# GKmini_SMD_final.net
KiCad netlist of a schematic drawn in EAGLE
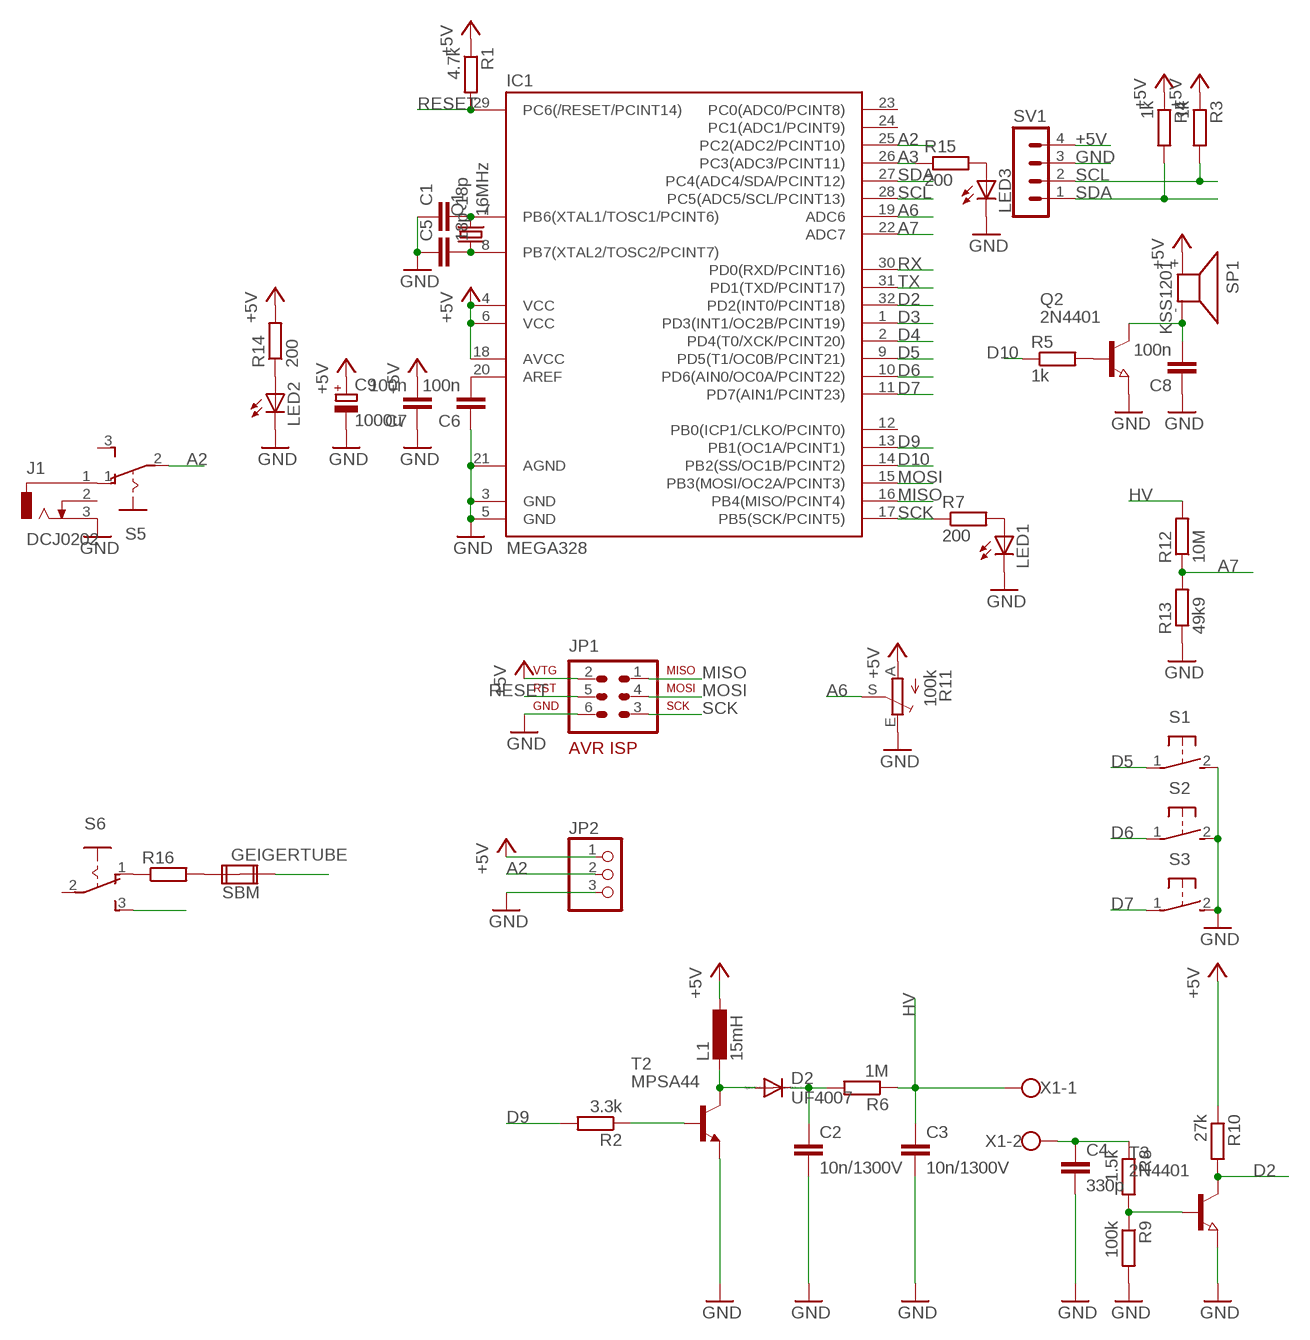
[diagram p0: schematic, sheet 1]

(export (version "E")
  (design (tool "Eeschema 10.0.6"))
  (components
    (comp (ref "C1")
      (value "18p")
      (footprint "eagle-import:C0805")
      (libsource (lib "eagle-import") (part "C-EUC0805"))
    )
    (comp (ref "C2")
      (value "10n/1300V")
      (footprint "eagle-import:C150-054X183")
      (libsource (lib "eagle-import") (part "rcl-igi_C-EU150-054X183"))
    )
    (comp (ref "C3")
      (value "10n/1300V")
      (footprint "eagle-import:C150-054X183")
      (libsource (lib "eagle-import") (part "rcl-igi_C-EU150-054X183"))
    )
    (comp (ref "C4")
      (value "330p")
      (footprint "eagle-import:C0805K")
      (libsource (lib "eagle-import") (part "C-EUC0805K"))
    )
    (comp (ref "C5")
      (value "18p")
      (footprint "eagle-import:C0805")
      (libsource (lib "eagle-import") (part "C-EUC0805"))
    )
    (comp (ref "C6")
      (value "100n")
      (footprint "eagle-import:C0805")
      (libsource (lib "eagle-import") (part "C-EUC0805"))
    )
    (comp (ref "C7")
      (value "100n")
      (footprint "eagle-import:C0805")
      (libsource (lib "eagle-import") (part "C-EUC0805"))
    )
    (comp (ref "C8")
      (value "100n")
      (footprint "eagle-import:C0805")
      (libsource (lib "eagle-import") (part "C-EUC0805"))
    )
    (comp (ref "C9")
      (value "1000u")
      (footprint "eagle-import:153CLV-1012")
      (libsource (lib "eagle-import") (part "CPOL-EU153CLV-1012"))
    )
    (comp (ref "D2")
      (value "UF4007")
      (footprint "eagle-import:C1702-05")
      (libsource (lib "eagle-import") (part "DIODE-C1702-05"))
    )
    (comp (ref "GEIGERTUBE")
      (value "SBM")
      (footprint "eagle-import:SBM")
      (libsource (lib "eagle-import") (part "SBM21"))
    )
    (comp (ref "IC1")
      (value "MEGA328")
      (footprint "eagle-import:TQFP32-08")
      (libsource (lib "eagle-import") (part "MEGA48/88/168-AU"))
    )
    (comp (ref "J1")
      (value "DCJ0202")
      (footprint "eagle-import:DCJ0202")
      (libsource (lib "eagle-import") (part "DCJ0202"))
    )
    (comp (ref "JP1")
      (value "AVR-ISP-6R")
      (footprint "eagle-import:AVR-ISP-6R")
      (libsource (lib "eagle-import") (part "AVR-ISP-6R"))
    )
    (comp (ref "JP2")
      (value "PINHD-1X3")
      (footprint "eagle-import:1X03")
      (libsource (lib "eagle-import") (part "PINHD-1X3"))
    )
    (comp (ref "L1")
      (value "15mH")
      (footprint "eagle-import:6000-XXXX-RC")
      (libsource (lib "eagle-import") (part "L-EU6000-XXX-RC"))
    )
    (comp (ref "LED1")
      (value "LED3MM")
      (footprint "eagle-import:LED3MM")
      (libsource (lib "eagle-import") (part "LED3MM"))
    )
    (comp (ref "LED2")
      (value "LED3MM")
      (footprint "eagle-import:LED3MM")
      (libsource (lib "eagle-import") (part "LED3MM"))
    )
    (comp (ref "LED3")
      (value "LED3MM")
      (footprint "eagle-import:LED3MM")
      (libsource (lib "eagle-import") (part "LED3MM"))
    )
    (comp (ref "Q1")
      (value "16MHz")
      (footprint "eagle-import:HC49UP")
      (libsource (lib "eagle-import") (part "CRYSTALHC49UP"))
    )
    (comp (ref "Q2")
      (value "2N4401")
      (footprint "eagle-import:SOT23W")
      (libsource (lib "eagle-import") (part "NPN-TRANSISTOR_SOT23W"))
    )
    (comp (ref "R1")
      (value "4.7k")
      (footprint "eagle-import:R0805")
      (libsource (lib "eagle-import") (part "R-EU_R0805"))
    )
    (comp (ref "R2")
      (value "3.3k")
      (footprint "eagle-import:R0805")
      (libsource (lib "eagle-import") (part "R-EU_R0805"))
    )
    (comp (ref "R3")
      (value "1k")
      (footprint "eagle-import:R0805")
      (libsource (lib "eagle-import") (part "R-EU_R0805"))
    )
    (comp (ref "R4")
      (value "1k")
      (footprint "eagle-import:R0805")
      (libsource (lib "eagle-import") (part "R-EU_R0805"))
    )
    (comp (ref "R5")
      (value "1k")
      (footprint "eagle-import:R0805")
      (libsource (lib "eagle-import") (part "R-EU_R0805"))
    )
    (comp (ref "R6")
      (value "1M")
      (footprint "eagle-import:0207_5V")
      (libsource (lib "eagle-import") (part "rcl-igi_R-EU_0207/5V"))
    )
    (comp (ref "R7")
      (value "200")
      (footprint "eagle-import:R0805")
      (libsource (lib "eagle-import") (part "R-EU_R0805"))
    )
    (comp (ref "R8")
      (value "1.5k")
      (footprint "eagle-import:R0805W")
      (libsource (lib "eagle-import") (part "R-EU_R0805W"))
    )
    (comp (ref "R9")
      (value "100k")
      (footprint "eagle-import:R0805W")
      (libsource (lib "eagle-import") (part "R-EU_R0805W"))
    )
    (comp (ref "R10")
      (value "27k")
      (footprint "eagle-import:R0805W")
      (libsource (lib "eagle-import") (part "R-EU_R0805W"))
    )
    (comp (ref "R11")
      (value "100k")
      (footprint "eagle-import:S64Y")
      (libsource (lib "eagle-import") (part "TRIM_EU-S64Y"))
    )
    (comp (ref "R12")
      (value "10M")
      (footprint "eagle-import:R0805")
      (libsource (lib "eagle-import") (part "R-EU_R0805"))
    )
    (comp (ref "R13")
      (value "49k9")
      (footprint "eagle-import:R0805")
      (libsource (lib "eagle-import") (part "R-EU_R0805"))
    )
    (comp (ref "R14")
      (value "200")
      (footprint "eagle-import:R0805")
      (libsource (lib "eagle-import") (part "R-EU_R0805"))
    )
    (comp (ref "R15")
      (value "200")
      (footprint "eagle-import:R0805")
      (libsource (lib "eagle-import") (part "R-EU_R0805"))
    )
    (comp (ref "R16")
      (value "R-EU_R1206W")
      (footprint "eagle-import:R1206W")
      (libsource (lib "eagle-import") (part "resistor_R-EU_R1206W"))
    )
    (comp (ref "S1")
      (value "31-XX")
      (footprint "eagle-import:B3F-31XX")
      (fields (field (name "MPN") "B3F-3100"))
      (libsource (lib "eagle-import") (part "31-XX"))
    )
    (comp (ref "S2")
      (value "31-XX")
      (footprint "eagle-import:B3F-31XX")
      (fields (field (name "MPN") "B3F-3100"))
      (libsource (lib "eagle-import") (part "31-XX"))
    )
    (comp (ref "S3")
      (value "31-XX")
      (footprint "eagle-import:B3F-31XX")
      (fields (field (name "MPN") "B3F-3100"))
      (libsource (lib "eagle-import") (part "31-XX"))
    )
    (comp (ref "S5")
      (value "255SB")
      (footprint "eagle-import:255SB")
      (libsource (lib "eagle-import") (part "255SB"))
    )
    (comp (ref "S6")
      (value "255SB")
      (footprint "eagle-import:255SB")
      (libsource (lib "eagle-import") (part "255SB"))
    )
    (comp (ref "SP1")
      (value "KSS1201")
      (footprint "eagle-import:KSS1201")
      (libsource (lib "eagle-import") (part "KSS1201"))
    )
    (comp (ref "SV1")
      (value "MA04-1")
      (footprint "eagle-import:MA04-1")
      (libsource (lib "eagle-import") (part "MA04-1"))
    )
    (comp (ref "T2")
      (value "MPSA44")
      (footprint "eagle-import:TO92-EBC-OVAL")
      (libsource (lib "eagle-import") (part "2N2222"))
    )
    (comp (ref "T3")
      (value "2N4401")
      (footprint "eagle-import:SOT23W")
      (libsource (lib "eagle-import") (part "NPN-TRANSISTOR_SOT23W"))
    )
    (comp (ref "X1")
      (value "W237-102")
      (footprint "eagle-import:W237-102")
      (fields (field (name "MPN") "237-102"))
      (libsource (lib "eagle-import") (part "W237-102"))
    )
  )
  (nets
    (net (code "1") (name "+5V") (class "Default")
      (node (ref "C7") (pin "2") (pinfunction "2_2") (pintype "passive"))
      (node (ref "C9") (pin "+") (pinfunction "+_+") (pintype "passive"))
      (node (ref "IC1") (pin "18") (pinfunction "AVCC_18") (pintype "passive"))
      (node (ref "IC1") (pin "4") (pinfunction "VCC_4") (pintype "power_in"))
      (node (ref "IC1") (pin "6") (pinfunction "VCC_6") (pintype "power_in"))
      (node (ref "JP1") (pin "2") (pinfunction "2_2") (pintype "passive"))
      (node (ref "JP2") (pin "1") (pinfunction "1_1") (pintype "passive"))
      (node (ref "L1") (pin "1") (pinfunction "1_1") (pintype "passive"))
      (node (ref "R1") (pin "1") (pinfunction "1_1") (pintype "passive"))
      (node (ref "R10") (pin "1") (pinfunction "1_1") (pintype "passive"))
      (node (ref "R11") (pin "A") (pinfunction "A_A") (pintype "passive"))
      (node (ref "R14") (pin "2") (pinfunction "2_2") (pintype "passive"))
      (node (ref "R3") (pin "1") (pinfunction "1_1") (pintype "passive"))
      (node (ref "R4") (pin "1") (pinfunction "1_1") (pintype "passive"))
      (node (ref "SP1") (pin "+") (pinfunction "1_+") (pintype "passive"))
      (node (ref "SV1") (pin "4") (pinfunction "4_4") (pintype "passive"))
    )
    (net (code "2") (name "/A2") (class "Default")
      (node (ref "IC1") (pin "25") (pinfunction "PC2(ADC2/PCINT10)_25") (pintype "bidirectional"))
      (node (ref "JP2") (pin "2") (pinfunction "2_2") (pintype "passive"))
      (node (ref "S5") (pin "2") (pinfunction "P_2") (pintype "passive"))
    )
    (net (code "3") (name "/A3") (class "Default")
      (node (ref "IC1") (pin "26") (pinfunction "PC3(ADC3/PCINT11)_26") (pintype "bidirectional"))
      (node (ref "R15") (pin "1") (pinfunction "1_1") (pintype "passive"))
    )
    (net (code "4") (name "/A6") (class "Default")
      (node (ref "IC1") (pin "19") (pinfunction "ADC6_19") (pintype "passive"))
      (node (ref "R11") (pin "S") (pinfunction "S_S") (pintype "passive"))
    )
    (net (code "5") (name "/A7") (class "Default")
      (node (ref "IC1") (pin "22") (pinfunction "ADC7_22") (pintype "passive"))
      (node (ref "R12") (pin "1") (pinfunction "1_1") (pintype "passive"))
      (node (ref "R13") (pin "2") (pinfunction "2_2") (pintype "passive"))
    )
    (net (code "6") (name "/D2") (class "Default")
      (node (ref "IC1") (pin "32") (pinfunction "PD2(INT0/PCINT18)_32") (pintype "bidirectional"))
      (node (ref "R10") (pin "2") (pinfunction "2_2") (pintype "passive"))
      (node (ref "T3") (pin "2") (pinfunction "C_2") (pintype "passive"))
    )
    (net (code "7") (name "/D3") (class "Default")
      (node (ref "IC1") (pin "1") (pinfunction "PD3(INT1/OC2B/PCINT19)_1") (pintype "bidirectional"))
    )
    (net (code "8") (name "/D4") (class "Default")
      (node (ref "IC1") (pin "2") (pinfunction "PD4(T0/XCK/PCINT20)_2") (pintype "bidirectional"))
    )
    (net (code "9") (name "/D5") (class "Default")
      (node (ref "IC1") (pin "9") (pinfunction "PD5(T1/OC0B/PCINT21)_9") (pintype "bidirectional"))
      (node (ref "S1") (pin "1") (pinfunction "P_1") (pintype "passive"))
    )
    (net (code "10") (name "/D6") (class "Default")
      (node (ref "IC1") (pin "10") (pinfunction "PD6(AIN0/OC0A/PCINT22)_10") (pintype "bidirectional"))
      (node (ref "S2") (pin "1") (pinfunction "P_1") (pintype "passive"))
    )
    (net (code "11") (name "/D7") (class "Default")
      (node (ref "IC1") (pin "11") (pinfunction "PD7(AIN1/PCINT23)_11") (pintype "bidirectional"))
      (node (ref "S3") (pin "1") (pinfunction "P_1") (pintype "passive"))
    )
    (net (code "12") (name "/D9") (class "Default")
      (node (ref "IC1") (pin "13") (pinfunction "PB1(OC1A/PCINT1)_13") (pintype "bidirectional"))
      (node (ref "R2") (pin "2") (pinfunction "2_2") (pintype "passive"))
    )
    (net (code "13") (name "/D10") (class "Default")
      (node (ref "IC1") (pin "14") (pinfunction "PB2(SS/OC1B/PCINT2)_14") (pintype "bidirectional"))
      (node (ref "R5") (pin "1") (pinfunction "1_1") (pintype "passive"))
    )
    (net (code "14") (name "/HV") (class "Default")
      (node (ref "C3") (pin "1") (pinfunction "1_1") (pintype "passive"))
      (node (ref "R12") (pin "2") (pinfunction "2_2") (pintype "passive"))
      (node (ref "R6") (pin "1") (pinfunction "1_1") (pintype "passive"))
      (node (ref "X1") (pin "1") (pinfunction "KL_1") (pintype "passive"))
    )
    (net (code "15") (name "/MISO") (class "Default")
      (node (ref "IC1") (pin "16") (pinfunction "PB4(MISO/PCINT4)_16") (pintype "bidirectional"))
      (node (ref "JP1") (pin "1") (pinfunction "1_1") (pintype "passive"))
    )
    (net (code "16") (name "/MOSI") (class "Default")
      (node (ref "IC1") (pin "15") (pinfunction "PB3(MOSI/OC2A/PCINT3)_15") (pintype "bidirectional"))
      (node (ref "JP1") (pin "4") (pinfunction "4_4") (pintype "passive"))
    )
    (net (code "17") (name "/RESET") (class "Default")
      (node (ref "IC1") (pin "29") (pinfunction "PC6(/RESET/PCINT14)_29") (pintype "bidirectional"))
      (node (ref "JP1") (pin "5") (pinfunction "5_5") (pintype "passive"))
      (node (ref "R1") (pin "2") (pinfunction "2_2") (pintype "passive"))
    )
    (net (code "18") (name "/RX") (class "Default")
      (node (ref "IC1") (pin "30") (pinfunction "PD0(RXD/PCINT16)_30") (pintype "bidirectional"))
    )
    (net (code "19") (name "/SCK") (class "Default")
      (node (ref "IC1") (pin "17") (pinfunction "PB5(SCK/PCINT5)_17") (pintype "bidirectional"))
      (node (ref "JP1") (pin "3") (pinfunction "3_3") (pintype "passive"))
      (node (ref "R7") (pin "1") (pinfunction "1_1") (pintype "passive"))
    )
    (net (code "20") (name "/SCL") (class "Default")
      (node (ref "IC1") (pin "28") (pinfunction "PC5(ADC5/SCL/PCINT13)_28") (pintype "bidirectional"))
      (node (ref "R3") (pin "2") (pinfunction "2_2") (pintype "passive"))
      (node (ref "SV1") (pin "2") (pinfunction "2_2") (pintype "passive"))
    )
    (net (code "21") (name "/SDA") (class "Default")
      (node (ref "IC1") (pin "27") (pinfunction "PC4(ADC4/SDA/PCINT12)_27") (pintype "bidirectional"))
      (node (ref "R4") (pin "2") (pinfunction "2_2") (pintype "passive"))
      (node (ref "SV1") (pin "1") (pinfunction "1_1") (pintype "passive"))
    )
    (net (code "22") (name "/TX") (class "Default")
      (node (ref "IC1") (pin "31") (pinfunction "PD1(TXD/PCINT17)_31") (pintype "bidirectional"))
    )
    (net (code "23") (name "GND") (class "Default")
      (node (ref "C1") (pin "1") (pinfunction "1_1") (pintype "passive"))
      (node (ref "C2") (pin "2") (pinfunction "2_2") (pintype "passive"))
      (node (ref "C3") (pin "2") (pinfunction "2_2") (pintype "passive"))
      (node (ref "C4") (pin "2") (pinfunction "2_2") (pintype "passive"))
      (node (ref "C5") (pin "1") (pinfunction "1_1") (pintype "passive"))
      (node (ref "C6") (pin "1") (pinfunction "1_1") (pintype "passive"))
      (node (ref "C7") (pin "1") (pinfunction "1_1") (pintype "passive"))
      (node (ref "C8") (pin "1") (pinfunction "1_1") (pintype "passive"))
      (node (ref "C9") (pin "-") (pinfunction "-_-") (pintype "passive"))
      (node (ref "IC1") (pin "21") (pinfunction "AGND_21") (pintype "power_in"))
      (node (ref "IC1") (pin "3") (pinfunction "GND_3") (pintype "power_in"))
      (node (ref "IC1") (pin "5") (pinfunction "GND_5") (pintype "power_in"))
      (node (ref "J1") (pin "3") (pinfunction "3_3") (pintype "passive"))
      (node (ref "JP1") (pin "6") (pinfunction "6_6") (pintype "passive"))
      (node (ref "JP2") (pin "3") (pinfunction "3_3") (pintype "passive"))
      (node (ref "LED1") (pin "K") (pinfunction "C_K") (pintype "passive"))
      (node (ref "LED2") (pin "K") (pinfunction "C_K") (pintype "passive"))
      (node (ref "LED3") (pin "K") (pinfunction "C_K") (pintype "passive"))
      (node (ref "Q2") (pin "3") (pinfunction "E_3") (pintype "passive"))
      (node (ref "R11") (pin "E") (pinfunction "E_E") (pintype "passive"))
      (node (ref "R13") (pin "1") (pinfunction "1_1") (pintype "passive"))
      (node (ref "R9") (pin "2") (pinfunction "2_2") (pintype "passive"))
      (node (ref "S1") (pin "2") (pinfunction "S_2") (pintype "passive"))
      (node (ref "S2") (pin "2") (pinfunction "S_2") (pintype "passive"))
      (node (ref "S3") (pin "2") (pinfunction "S_2") (pintype "passive"))
      (node (ref "SV1") (pin "3") (pinfunction "3_3") (pintype "passive"))
      (node (ref "T2") (pin "E") (pinfunction "E_E") (pintype "passive"))
      (node (ref "T3") (pin "3") (pinfunction "E_3") (pintype "passive"))
    )
    (net (code "24") (name "Net-(C2-Pad1)") (class "Default")
      (node (ref "C2") (pin "1") (pinfunction "1_1") (pintype "passive"))
      (node (ref "D2") (pin "C") (pinfunction "C_C") (pintype "passive"))
      (node (ref "R6") (pin "2") (pinfunction "2_2") (pintype "passive"))
    )
    (net (code "25") (name "Net-(D2-PadA)") (class "Default")
      (node (ref "D2") (pin "A") (pinfunction "A_A") (pintype "passive"))
      (node (ref "L1") (pin "2") (pinfunction "2_2") (pintype "passive"))
      (node (ref "T2") (pin "C") (pinfunction "C_C") (pintype "passive"))
    )
    (net (code "26") (name "Net-(GEIGERTUBE-Pad1A)") (class "Default")
      (node (ref "GEIGERTUBE") (pin "1A") (pinfunction "1A_1A") (pintype "passive"))
      (node (ref "R16") (pin "2") (pinfunction "2_2") (pintype "passive"))
    )
    (net (code "27") (name "Net-(IC1-AREF)") (class "Default")
      (node (ref "C6") (pin "2") (pinfunction "2_2") (pintype "passive"))
      (node (ref "IC1") (pin "20") (pinfunction "AREF_20") (pintype "passive"))
    )
    (net (code "28") (name "Net-(IC1-PB6(XTAL1{slash}TOSC1{slash}PCINT6))") (class "Default")
      (node (ref "C1") (pin "2") (pinfunction "2_2") (pintype "passive"))
      (node (ref "IC1") (pin "7") (pinfunction "PB6(XTAL1/TOSC1/PCINT6)_7") (pintype "bidirectional"))
      (node (ref "Q1") (pin "2") (pinfunction "2_2") (pintype "passive"))
    )
    (net (code "29") (name "Net-(IC1-PB7(XTAL2{slash}TOSC2{slash}PCINT7))") (class "Default")
      (node (ref "C5") (pin "2") (pinfunction "2_2") (pintype "passive"))
      (node (ref "IC1") (pin "8") (pinfunction "PB7(XTAL2/TOSC2/PCINT7)_8") (pintype "bidirectional"))
      (node (ref "Q1") (pin "1") (pinfunction "1_1") (pintype "passive"))
    )
    (net (code "30") (name "Net-(LED1-PadA)") (class "Default")
      (node (ref "LED1") (pin "A") (pinfunction "A_A") (pintype "passive"))
      (node (ref "R7") (pin "2") (pinfunction "2_2") (pintype "passive"))
    )
    (net (code "31") (name "Net-(LED2-PadA)") (class "Default")
      (node (ref "LED2") (pin "A") (pinfunction "A_A") (pintype "passive"))
      (node (ref "R14") (pin "1") (pinfunction "1_1") (pintype "passive"))
    )
    (net (code "32") (name "Net-(LED3-PadA)") (class "Default")
      (node (ref "LED3") (pin "A") (pinfunction "A_A") (pintype "passive"))
      (node (ref "R15") (pin "2") (pinfunction "2_2") (pintype "passive"))
    )
    (net (code "33") (name "Net-(Q2-B)") (class "Default")
      (node (ref "Q2") (pin "1") (pinfunction "B_1") (pintype "passive"))
      (node (ref "R5") (pin "2") (pinfunction "2_2") (pintype "passive"))
    )
    (net (code "34") (name "Net-(Q2-C)") (class "Default")
      (node (ref "C8") (pin "2") (pinfunction "2_2") (pintype "passive"))
      (node (ref "Q2") (pin "2") (pinfunction "C_2") (pintype "passive"))
      (node (ref "SP1") (pin "-") (pinfunction "2_-") (pintype "passive"))
    )
    (net (code "35") (name "Net-(R2-Pad1)") (class "Default")
      (node (ref "R2") (pin "1") (pinfunction "1_1") (pintype "passive"))
      (node (ref "T2") (pin "B") (pinfunction "B_B") (pintype "passive"))
    )
    (net (code "36") (name "Net-(S5-O)") (class "Default")
      (node (ref "J1") (pin "1") (pinfunction "1_1") (pintype "passive"))
      (node (ref "S5") (pin "1") (pinfunction "O_1") (pintype "passive"))
    )
    (net (code "37") (name "Net-(S6-O)") (class "Default")
      (node (ref "R16") (pin "1") (pinfunction "1_1") (pintype "passive"))
      (node (ref "S6") (pin "1") (pinfunction "O_1") (pintype "passive"))
    )
    (net (code "38") (name "Net-(T3-B)") (class "Default")
      (node (ref "R8") (pin "2") (pinfunction "2_2") (pintype "passive"))
      (node (ref "R9") (pin "1") (pinfunction "1_1") (pintype "passive"))
      (node (ref "T3") (pin "1") (pinfunction "B_1") (pintype "passive"))
    )
    (net (code "39") (name "Net-(X1B-KL)") (class "Default")
      (node (ref "C4") (pin "1") (pinfunction "1_1") (pintype "passive"))
      (node (ref "R8") (pin "1") (pinfunction "1_1") (pintype "passive"))
      (node (ref "X1") (pin "2") (pinfunction "KL_2") (pintype "passive"))
    )
    (net (code "40") (name "unconnected-(GEIGERTUBE-Pad1B)") (class "Default")
      (node (ref "GEIGERTUBE") (pin "1B") (pinfunction "1B_1B") (pintype "passive"))
    )
    (net (code "41") (name "unconnected-(GEIGERTUBE-Pad2A)") (class "Default")
      (node (ref "GEIGERTUBE") (pin "2A") (pinfunction "2A_2A") (pintype "passive"))
    )
    (net (code "42") (name "unconnected-(GEIGERTUBE-Pad2B)") (class "Default")
      (node (ref "GEIGERTUBE") (pin "2B") (pinfunction "2B_2B") (pintype "passive"))
    )
    (net (code "43") (name "unconnected-(IC1-PB0(ICP1{slash}CLKO{slash}PCINT0)-Pad12)") (class "Default")
      (node (ref "IC1") (pin "12") (pinfunction "PB0(ICP1/CLKO/PCINT0)_12") (pintype "bidirectional"))
    )
    (net (code "44") (name "unconnected-(IC1-PC0(ADC0{slash}PCINT8)-Pad23)") (class "Default")
      (node (ref "IC1") (pin "23") (pinfunction "PC0(ADC0/PCINT8)_23") (pintype "bidirectional"))
    )
    (net (code "45") (name "unconnected-(IC1-PC1(ADC1{slash}PCINT9)-Pad24)") (class "Default")
      (node (ref "IC1") (pin "24") (pinfunction "PC1(ADC1/PCINT9)_24") (pintype "bidirectional"))
    )
    (net (code "46") (name "unconnected-(J1-Pad2)") (class "Default")
      (node (ref "J1") (pin "2") (pinfunction "2_2") (pintype "passive"))
    )
    (net (code "47") (name "unconnected-(S5-S-Pad3)") (class "Default")
      (node (ref "S5") (pin "3") (pinfunction "S_3") (pintype "passive"))
    )
    (net (code "48") (name "unconnected-(S6-P-Pad2)") (class "Default")
      (node (ref "S6") (pin "2") (pinfunction "P_2") (pintype "passive"))
    )
    (net (code "49") (name "unconnected-(S6-S-Pad3)") (class "Default")
      (node (ref "S6") (pin "3") (pinfunction "S_3") (pintype "passive"))
    )
  )
)
